# main_P2100.net
KiCad netlist of a schematic drawn in EAGLE
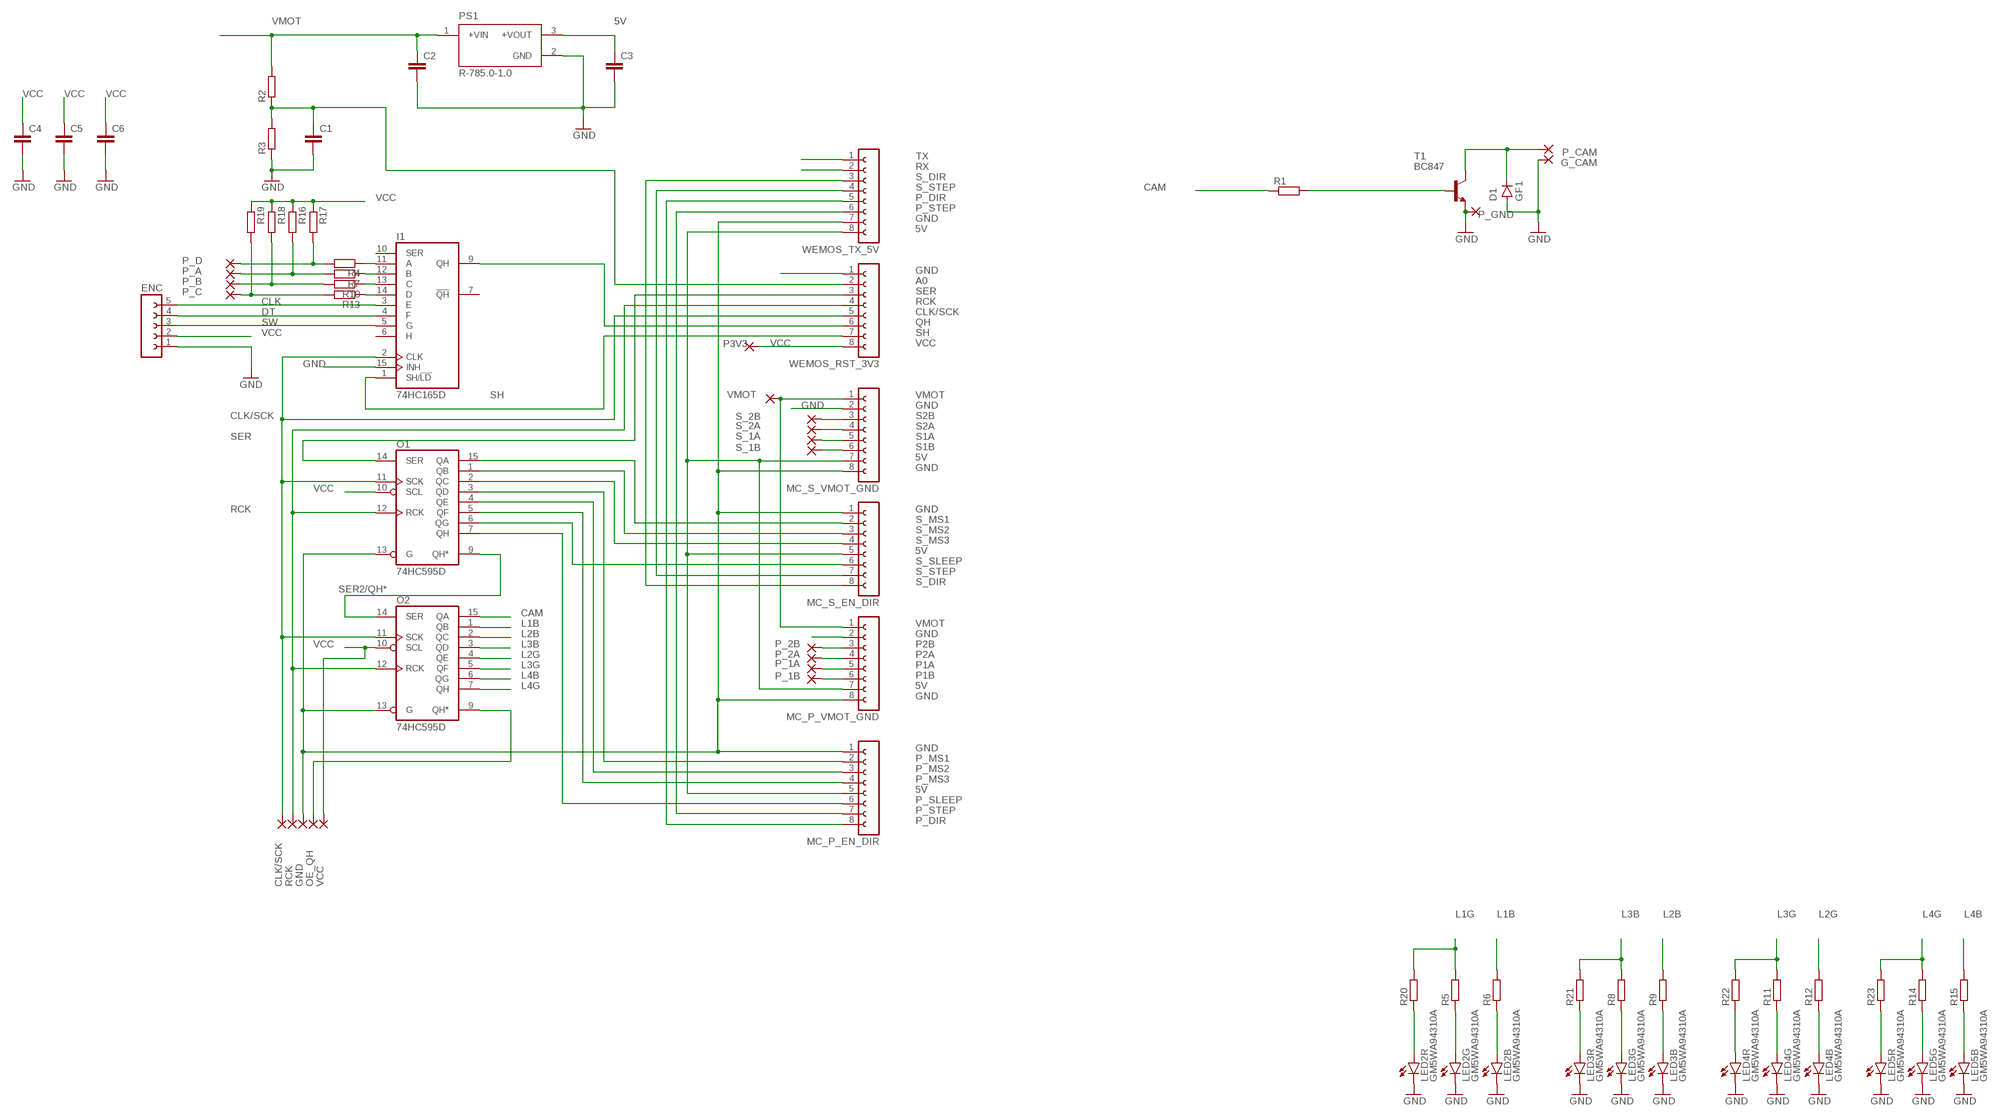
[diagram p0: schematic, sheet 1]

(export (version "E")
  (design (tool "Eeschema 10.0.6"))
  (components
    (comp (ref "C1")
      (value "C-EUC0603")
      (footprint "eagle-import:C0603")
      (libsource (lib "eagle-import") (part "C-EUC0603"))
    )
    (comp (ref "C2")
      (value "C-EUC1206")
      (footprint "eagle-import:C1206")
      (libsource (lib "eagle-import") (part "C-EUC1206"))
    )
    (comp (ref "C3")
      (value "C-EUC1206")
      (footprint "eagle-import:C1206")
      (libsource (lib "eagle-import") (part "C-EUC1206"))
    )
    (comp (ref "C4")
      (value "C-EUC0603")
      (footprint "eagle-import:C0603")
      (libsource (lib "eagle-import") (part "C-EUC0603"))
    )
    (comp (ref "C5")
      (value "C-EUC0603")
      (footprint "eagle-import:C0603")
      (libsource (lib "eagle-import") (part "C-EUC0603"))
    )
    (comp (ref "C6")
      (value "C-EUC0603")
      (footprint "eagle-import:C0603")
      (libsource (lib "eagle-import") (part "C-EUC0603"))
    )
    (comp (ref "D1")
      (value "GF1")
      (footprint "eagle-import:SMA-DO214AC")
      (libsource (lib "eagle-import") (part "GF1"))
    )
    (comp (ref "ENC")
      (value "FE05-1")
      (footprint "eagle-import:FE05-1")
      (libsource (lib "eagle-import") (part "FE05-1"))
    )
    (comp (ref "G_CAM")
      (value "SMD5")
      (footprint "eagle-import:SMD2,54-5,08")
      (libsource (lib "eagle-import") (part "SMD5"))
    )
    (comp (ref "I1")
      (value "74HC165D")
      (footprint "eagle-import:SO16")
      (libsource (lib "eagle-import") (part "74165DHC"))
    )
    (comp (ref "LED2")
      (value "GM5WA94310A")
      (footprint "eagle-import:GM5WA94310A")
      (libsource (lib "eagle-import") (part "GM5WA94310A"))
    )
    (comp (ref "LED3")
      (value "GM5WA94310A")
      (footprint "eagle-import:GM5WA94310A")
      (libsource (lib "eagle-import") (part "GM5WA94310A"))
    )
    (comp (ref "LED4")
      (value "GM5WA94310A")
      (footprint "eagle-import:GM5WA94310A")
      (libsource (lib "eagle-import") (part "GM5WA94310A"))
    )
    (comp (ref "LED5")
      (value "GM5WA94310A")
      (footprint "eagle-import:GM5WA94310A")
      (libsource (lib "eagle-import") (part "GM5WA94310A"))
    )
    (comp (ref "MC_P_EN_DIR")
      (value "FE08-1")
      (footprint "eagle-import:FE08")
      (libsource (lib "eagle-import") (part "FE08-1"))
    )
    (comp (ref "MC_P_VMOT_GND")
      (value "FE08-1")
      (footprint "eagle-import:FE08")
      (libsource (lib "eagle-import") (part "FE08-1"))
    )
    (comp (ref "MC_S_EN_DIR")
      (value "FE08-1")
      (footprint "eagle-import:FE08")
      (libsource (lib "eagle-import") (part "FE08-1"))
    )
    (comp (ref "MC_S_VMOT_GND")
      (value "FE08-1")
      (footprint "eagle-import:FE08")
      (libsource (lib "eagle-import") (part "FE08-1"))
    )
    (comp (ref "O1")
      (value "74HC595D")
      (footprint "eagle-import:SO16")
      (libsource (lib "eagle-import") (part "74595DHC"))
    )
    (comp (ref "O2")
      (value "74HC595D")
      (footprint "eagle-import:SO16")
      (libsource (lib "eagle-import") (part "74595DHC"))
    )
    (comp (ref "P3V3")
      (value "SMD5")
      (footprint "eagle-import:SMD2,54-5,08")
      (libsource (lib "eagle-import") (part "SMD5"))
    )
    (comp (ref "PS1")
      (value "R-785.0-1.0")
      (footprint "eagle-import:CONV_R-785.0-1.0")
      (fields (field (name "MF") "Recom Power"))
      (libsource (lib "eagle-import") (part "R-785.0-1.0"))
    )
    (comp (ref "P_1A")
      (value "SMD5")
      (footprint "eagle-import:SMD2,54-5,08")
      (libsource (lib "eagle-import") (part "SMD5"))
    )
    (comp (ref "P_1B")
      (value "SMD5")
      (footprint "eagle-import:SMD2,54-5,08")
      (libsource (lib "eagle-import") (part "SMD5"))
    )
    (comp (ref "P_1B1")
      (value "SMD5")
      (footprint "eagle-import:SMD2,54-5,08")
      (libsource (lib "eagle-import") (part "SMD5"))
    )
    (comp (ref "P_1B2")
      (value "SMD5")
      (footprint "eagle-import:SMD2,54-5,08")
      (libsource (lib "eagle-import") (part "SMD5"))
    )
    (comp (ref "P_1B3")
      (value "SMD5")
      (footprint "eagle-import:SMD2,54-5,08")
      (libsource (lib "eagle-import") (part "SMD5"))
    )
    (comp (ref "P_1B4")
      (value "SMD5")
      (footprint "eagle-import:SMD2,54-5,08")
      (libsource (lib "eagle-import") (part "SMD5"))
    )
    (comp (ref "P_1B5")
      (value "SMD5")
      (footprint "eagle-import:SMD2,54-5,08")
      (libsource (lib "eagle-import") (part "SMD5"))
    )
    (comp (ref "P_2A")
      (value "SMD5")
      (footprint "eagle-import:SMD2,54-5,08")
      (libsource (lib "eagle-import") (part "SMD5"))
    )
    (comp (ref "P_2B")
      (value "SMD5")
      (footprint "eagle-import:SMD2,54-5,08")
      (libsource (lib "eagle-import") (part "SMD5"))
    )
    (comp (ref "P_A")
      (value "SMD5")
      (footprint "eagle-import:SMD2,54-5,08")
      (libsource (lib "eagle-import") (part "SMD5"))
    )
    (comp (ref "P_B")
      (value "SMD5")
      (footprint "eagle-import:SMD2,54-5,08")
      (libsource (lib "eagle-import") (part "SMD5"))
    )
    (comp (ref "P_C")
      (value "SMD5")
      (footprint "eagle-import:SMD2,54-5,08")
      (libsource (lib "eagle-import") (part "SMD5"))
    )
    (comp (ref "P_CAM")
      (value "SMD5")
      (footprint "eagle-import:SMD2,54-5,08")
      (libsource (lib "eagle-import") (part "SMD5"))
    )
    (comp (ref "P_D")
      (value "SMD5")
      (footprint "eagle-import:SMD2,54-5,08")
      (libsource (lib "eagle-import") (part "SMD5"))
    )
    (comp (ref "P_GND")
      (value "SMD5")
      (footprint "eagle-import:SMD2,54-5,08")
      (libsource (lib "eagle-import") (part "SMD5"))
    )
    (comp (ref "R1")
      (value "R-EU_R0603")
      (footprint "eagle-import:R0603")
      (libsource (lib "eagle-import") (part "R-EU_R0603"))
    )
    (comp (ref "R2")
      (value "R-EU_R0603")
      (footprint "eagle-import:R0603")
      (libsource (lib "eagle-import") (part "R-EU_R0603"))
    )
    (comp (ref "R3")
      (value "R-EU_R0603")
      (footprint "eagle-import:R0603")
      (libsource (lib "eagle-import") (part "R-EU_R0603"))
    )
    (comp (ref "R4")
      (value "R-EU_R0603")
      (footprint "eagle-import:R0603")
      (libsource (lib "eagle-import") (part "R-EU_R0603"))
    )
    (comp (ref "R5")
      (value "R-EU_R0603")
      (footprint "eagle-import:R0603")
      (libsource (lib "eagle-import") (part "R-EU_R0603"))
    )
    (comp (ref "R6")
      (value "R-EU_R0603")
      (footprint "eagle-import:R0603")
      (libsource (lib "eagle-import") (part "R-EU_R0603"))
    )
    (comp (ref "R7")
      (value "R-EU_R0603")
      (footprint "eagle-import:R0603")
      (libsource (lib "eagle-import") (part "R-EU_R0603"))
    )
    (comp (ref "R8")
      (value "R-EU_R0603")
      (footprint "eagle-import:R0603")
      (libsource (lib "eagle-import") (part "R-EU_R0603"))
    )
    (comp (ref "R9")
      (value "R-EU_R0603")
      (footprint "eagle-import:R0603")
      (libsource (lib "eagle-import") (part "R-EU_R0603"))
    )
    (comp (ref "R10")
      (value "R-EU_R0603")
      (footprint "eagle-import:R0603")
      (libsource (lib "eagle-import") (part "R-EU_R0603"))
    )
    (comp (ref "R11")
      (value "R-EU_R0603")
      (footprint "eagle-import:R0603")
      (libsource (lib "eagle-import") (part "R-EU_R0603"))
    )
    (comp (ref "R12")
      (value "R-EU_R0603")
      (footprint "eagle-import:R0603")
      (libsource (lib "eagle-import") (part "R-EU_R0603"))
    )
    (comp (ref "R13")
      (value "R-EU_R0603")
      (footprint "eagle-import:R0603")
      (libsource (lib "eagle-import") (part "R-EU_R0603"))
    )
    (comp (ref "R14")
      (value "R-EU_R0603")
      (footprint "eagle-import:R0603")
      (libsource (lib "eagle-import") (part "R-EU_R0603"))
    )
    (comp (ref "R15")
      (value "R-EU_R0603")
      (footprint "eagle-import:R0603")
      (libsource (lib "eagle-import") (part "R-EU_R0603"))
    )
    (comp (ref "R16")
      (value "R-EU_R0603")
      (footprint "eagle-import:R0603")
      (libsource (lib "eagle-import") (part "R-EU_R0603"))
    )
    (comp (ref "R17")
      (value "R-EU_R0603")
      (footprint "eagle-import:R0603")
      (libsource (lib "eagle-import") (part "R-EU_R0603"))
    )
    (comp (ref "R18")
      (value "R-EU_R0603")
      (footprint "eagle-import:R0603")
      (libsource (lib "eagle-import") (part "R-EU_R0603"))
    )
    (comp (ref "R19")
      (value "R-EU_R0603")
      (footprint "eagle-import:R0603")
      (libsource (lib "eagle-import") (part "R-EU_R0603"))
    )
    (comp (ref "R20")
      (value "R-EU_R0603")
      (footprint "eagle-import:R0603")
      (libsource (lib "eagle-import") (part "R-EU_R0603"))
    )
    (comp (ref "R21")
      (value "R-EU_R0603")
      (footprint "eagle-import:R0603")
      (libsource (lib "eagle-import") (part "R-EU_R0603"))
    )
    (comp (ref "R22")
      (value "R-EU_R0603")
      (footprint "eagle-import:R0603")
      (libsource (lib "eagle-import") (part "R-EU_R0603"))
    )
    (comp (ref "R23")
      (value "R-EU_R0603")
      (footprint "eagle-import:R0603")
      (libsource (lib "eagle-import") (part "R-EU_R0603"))
    )
    (comp (ref "S_1A")
      (value "SMD5")
      (footprint "eagle-import:SMD2,54-5,08")
      (libsource (lib "eagle-import") (part "SMD5"))
    )
    (comp (ref "S_1B")
      (value "SMD5")
      (footprint "eagle-import:SMD2,54-5,08")
      (libsource (lib "eagle-import") (part "SMD5"))
    )
    (comp (ref "S_2A")
      (value "SMD5")
      (footprint "eagle-import:SMD2,54-5,08")
      (libsource (lib "eagle-import") (part "SMD5"))
    )
    (comp (ref "S_2B")
      (value "SMD5")
      (footprint "eagle-import:SMD2,54-5,08")
      (libsource (lib "eagle-import") (part "SMD5"))
    )
    (comp (ref "T1")
      (value "BC847")
      (footprint "eagle-import:SOT23")
      (libsource (lib "eagle-import") (part "BC847"))
    )
    (comp (ref "VMOT")
      (value "SMD5")
      (footprint "eagle-import:SMD2,54-5,08")
      (libsource (lib "eagle-import") (part "SMD5"))
    )
    (comp (ref "WEMOS_RST_3V3")
      (value "FE08-1")
      (footprint "eagle-import:FE08")
      (libsource (lib "eagle-import") (part "FE08-1"))
    )
    (comp (ref "WEMOS_TX_5V")
      (value "FE08-1")
      (footprint "eagle-import:FE08")
      (libsource (lib "eagle-import") (part "FE08-1"))
    )
  )
  (nets
    (net (code "1") (name "/5V") (class "Default")
      (node (ref "C3") (pin "1") (pinfunction "1_1") (pintype "passive"))
      (node (ref "MC_P_EN_DIR") (pin "5") (pinfunction "5_5") (pintype "passive"))
      (node (ref "MC_P_VMOT_GND") (pin "7") (pinfunction "7_7") (pintype "passive"))
      (node (ref "MC_S_EN_DIR") (pin "5") (pinfunction "5_5") (pintype "passive"))
      (node (ref "MC_S_VMOT_GND") (pin "7") (pinfunction "7_7") (pintype "passive"))
      (node (ref "PS1") (pin "3") (pinfunction "+VOUT_3") (pintype "output"))
      (node (ref "WEMOS_TX_5V") (pin "8") (pinfunction "8_8") (pintype "passive"))
    )
    (net (code "2") (name "/A0") (class "Default")
      (node (ref "C1") (pin "1") (pinfunction "1_1") (pintype "passive"))
      (node (ref "R2") (pin "1") (pinfunction "1_1") (pintype "passive"))
      (node (ref "R3") (pin "2") (pinfunction "2_2") (pintype "passive"))
      (node (ref "WEMOS_RST_3V3") (pin "2") (pinfunction "2_2") (pintype "passive"))
    )
    (net (code "3") (name "/CAM") (class "Default")
      (node (ref "O2") (pin "15") (pinfunction "QA_15") (pintype "tri_state"))
      (node (ref "R1") (pin "1") (pinfunction "1_1") (pintype "passive"))
    )
    (net (code "4") (name "/CLK") (class "Default")
      (node (ref "ENC") (pin "5") (pinfunction "5_5") (pintype "passive"))
      (node (ref "I1") (pin "3") (pinfunction "E_3") (pintype "input"))
    )
    (net (code "5") (name "/CLK{slash}SCK") (class "Default")
      (node (ref "I1") (pin "2") (pinfunction "CLK_2") (pintype "input"))
      (node (ref "O1") (pin "11") (pinfunction "SCK_11") (pintype "input"))
      (node (ref "O2") (pin "11") (pinfunction "SCK_11") (pintype "input"))
      (node (ref "P_1B1") (pin "1") (pinfunction "P_1") (pintype "passive"))
      (node (ref "WEMOS_RST_3V3") (pin "5") (pinfunction "5_5") (pintype "passive"))
    )
    (net (code "6") (name "/DT") (class "Default")
      (node (ref "ENC") (pin "4") (pinfunction "4_4") (pintype "passive"))
      (node (ref "I1") (pin "4") (pinfunction "F_4") (pintype "input"))
    )
    (net (code "7") (name "/L1B") (class "Default")
      (node (ref "O2") (pin "1") (pinfunction "QB_1") (pintype "tri_state"))
      (node (ref "R6") (pin "2") (pinfunction "2_2") (pintype "passive"))
    )
    (net (code "8") (name "/L1G") (class "Default")
      (node (ref "R20") (pin "2") (pinfunction "2_2") (pintype "passive"))
      (node (ref "R5") (pin "2") (pinfunction "2_2") (pintype "passive"))
    )
    (net (code "9") (name "/L2B") (class "Default")
      (node (ref "O2") (pin "2") (pinfunction "QC_2") (pintype "tri_state"))
      (node (ref "R9") (pin "2") (pinfunction "2_2") (pintype "passive"))
    )
    (net (code "10") (name "/L2G") (class "Default")
      (node (ref "O2") (pin "4") (pinfunction "QE_4") (pintype "tri_state"))
      (node (ref "R12") (pin "2") (pinfunction "2_2") (pintype "passive"))
    )
    (net (code "11") (name "/L3B") (class "Default")
      (node (ref "O2") (pin "3") (pinfunction "QD_3") (pintype "tri_state"))
      (node (ref "R21") (pin "2") (pinfunction "2_2") (pintype "passive"))
      (node (ref "R8") (pin "2") (pinfunction "2_2") (pintype "passive"))
    )
    (net (code "12") (name "/L3G") (class "Default")
      (node (ref "O2") (pin "5") (pinfunction "QF_5") (pintype "tri_state"))
      (node (ref "R11") (pin "2") (pinfunction "2_2") (pintype "passive"))
      (node (ref "R22") (pin "2") (pinfunction "2_2") (pintype "passive"))
    )
    (net (code "13") (name "/L4B") (class "Default")
      (node (ref "O2") (pin "6") (pinfunction "QG_6") (pintype "tri_state"))
      (node (ref "R15") (pin "2") (pinfunction "2_2") (pintype "passive"))
    )
    (net (code "14") (name "/L4G") (class "Default")
      (node (ref "O2") (pin "7") (pinfunction "QH_7") (pintype "tri_state"))
      (node (ref "R14") (pin "2") (pinfunction "2_2") (pintype "passive"))
      (node (ref "R23") (pin "2") (pinfunction "2_2") (pintype "passive"))
    )
    (net (code "15") (name "/OE_QH") (class "Default")
      (node (ref "O2") (pin "9") (pinfunction "QH*_9") (pintype "tri_state"))
      (node (ref "P_1B4") (pin "1") (pinfunction "P_1") (pintype "passive"))
    )
    (net (code "16") (name "/P1A") (class "Default")
      (node (ref "MC_P_VMOT_GND") (pin "5") (pinfunction "5_5") (pintype "passive"))
      (node (ref "P_1A") (pin "1") (pinfunction "P_1") (pintype "passive"))
    )
    (net (code "17") (name "/P1B") (class "Default")
      (node (ref "MC_P_VMOT_GND") (pin "6") (pinfunction "6_6") (pintype "passive"))
      (node (ref "P_1B") (pin "1") (pinfunction "P_1") (pintype "passive"))
    )
    (net (code "18") (name "/P2A") (class "Default")
      (node (ref "MC_P_VMOT_GND") (pin "4") (pinfunction "4_4") (pintype "passive"))
      (node (ref "P_2A") (pin "1") (pinfunction "P_1") (pintype "passive"))
    )
    (net (code "19") (name "/P2B") (class "Default")
      (node (ref "MC_P_VMOT_GND") (pin "3") (pinfunction "3_3") (pintype "passive"))
      (node (ref "P_2B") (pin "1") (pinfunction "P_1") (pintype "passive"))
    )
    (net (code "20") (name "/P_DIR") (class "Default")
      (node (ref "MC_P_EN_DIR") (pin "8") (pinfunction "8_8") (pintype "passive"))
      (node (ref "WEMOS_TX_5V") (pin "5") (pinfunction "5_5") (pintype "passive"))
    )
    (net (code "21") (name "/P_MS1") (class "Default")
      (node (ref "MC_P_EN_DIR") (pin "2") (pinfunction "2_2") (pintype "passive"))
      (node (ref "O1") (pin "3") (pinfunction "QD_3") (pintype "tri_state"))
    )
    (net (code "22") (name "/P_MS2") (class "Default")
      (node (ref "MC_P_EN_DIR") (pin "3") (pinfunction "3_3") (pintype "passive"))
      (node (ref "O1") (pin "4") (pinfunction "QE_4") (pintype "tri_state"))
    )
    (net (code "23") (name "/P_MS3") (class "Default")
      (node (ref "MC_P_EN_DIR") (pin "4") (pinfunction "4_4") (pintype "passive"))
      (node (ref "O1") (pin "5") (pinfunction "QF_5") (pintype "tri_state"))
    )
    (net (code "24") (name "/P_SLEEP") (class "Default")
      (node (ref "MC_P_EN_DIR") (pin "6") (pinfunction "6_6") (pintype "passive"))
      (node (ref "O1") (pin "7") (pinfunction "QH_7") (pintype "tri_state"))
    )
    (net (code "25") (name "/P_STEP") (class "Default")
      (node (ref "MC_P_EN_DIR") (pin "7") (pinfunction "7_7") (pintype "passive"))
      (node (ref "WEMOS_TX_5V") (pin "6") (pinfunction "6_6") (pintype "passive"))
    )
    (net (code "26") (name "/QH") (class "Default")
      (node (ref "I1") (pin "9") (pinfunction "QH_9") (pintype "output"))
      (node (ref "WEMOS_RST_3V3") (pin "6") (pinfunction "6_6") (pintype "passive"))
    )
    (net (code "27") (name "/RCK") (class "Default")
      (node (ref "O1") (pin "12") (pinfunction "RCK_12") (pintype "input"))
      (node (ref "O2") (pin "12") (pinfunction "RCK_12") (pintype "input"))
      (node (ref "P_1B2") (pin "1") (pinfunction "P_1") (pintype "passive"))
      (node (ref "WEMOS_RST_3V3") (pin "4") (pinfunction "4_4") (pintype "passive"))
    )
    (net (code "28") (name "/RX") (class "Default")
      (node (ref "WEMOS_TX_5V") (pin "2") (pinfunction "2_2") (pintype "passive"))
    )
    (net (code "29") (name "/S1A") (class "Default")
      (node (ref "MC_S_VMOT_GND") (pin "5") (pinfunction "5_5") (pintype "passive"))
      (node (ref "S_1A") (pin "1") (pinfunction "P_1") (pintype "passive"))
    )
    (net (code "30") (name "/S1B") (class "Default")
      (node (ref "MC_S_VMOT_GND") (pin "6") (pinfunction "6_6") (pintype "passive"))
      (node (ref "S_1B") (pin "1") (pinfunction "P_1") (pintype "passive"))
    )
    (net (code "31") (name "/S2A") (class "Default")
      (node (ref "MC_S_VMOT_GND") (pin "4") (pinfunction "4_4") (pintype "passive"))
      (node (ref "S_2A") (pin "1") (pinfunction "P_1") (pintype "passive"))
    )
    (net (code "32") (name "/S2B") (class "Default")
      (node (ref "MC_S_VMOT_GND") (pin "3") (pinfunction "3_3") (pintype "passive"))
      (node (ref "S_2B") (pin "1") (pinfunction "P_1") (pintype "passive"))
    )
    (net (code "33") (name "/SER") (class "Default")
      (node (ref "O1") (pin "14") (pinfunction "SER_14") (pintype "input"))
      (node (ref "WEMOS_RST_3V3") (pin "3") (pinfunction "3_3") (pintype "passive"))
    )
    (net (code "34") (name "/SER2{slash}QH*") (class "Default")
      (node (ref "O1") (pin "9") (pinfunction "QH*_9") (pintype "tri_state"))
      (node (ref "O2") (pin "14") (pinfunction "SER_14") (pintype "input"))
    )
    (net (code "35") (name "/SH") (class "Default")
      (node (ref "I1") (pin "1") (pinfunction "SH/~{LD}_1") (pintype "input"))
      (node (ref "WEMOS_RST_3V3") (pin "7") (pinfunction "7_7") (pintype "passive"))
    )
    (net (code "36") (name "/SW") (class "Default")
      (node (ref "ENC") (pin "3") (pinfunction "3_3") (pintype "passive"))
      (node (ref "I1") (pin "5") (pinfunction "G_5") (pintype "input"))
    )
    (net (code "37") (name "/S_DIR") (class "Default")
      (node (ref "MC_S_EN_DIR") (pin "8") (pinfunction "8_8") (pintype "passive"))
      (node (ref "WEMOS_TX_5V") (pin "3") (pinfunction "3_3") (pintype "passive"))
    )
    (net (code "38") (name "/S_MS1") (class "Default")
      (node (ref "MC_S_EN_DIR") (pin "2") (pinfunction "2_2") (pintype "passive"))
      (node (ref "O1") (pin "15") (pinfunction "QA_15") (pintype "tri_state"))
    )
    (net (code "39") (name "/S_MS2") (class "Default")
      (node (ref "MC_S_EN_DIR") (pin "3") (pinfunction "3_3") (pintype "passive"))
      (node (ref "O1") (pin "1") (pinfunction "QB_1") (pintype "tri_state"))
    )
    (net (code "40") (name "/S_MS3") (class "Default")
      (node (ref "MC_S_EN_DIR") (pin "4") (pinfunction "4_4") (pintype "passive"))
      (node (ref "O1") (pin "2") (pinfunction "QC_2") (pintype "tri_state"))
    )
    (net (code "41") (name "/S_SLEEP") (class "Default")
      (node (ref "MC_S_EN_DIR") (pin "6") (pinfunction "6_6") (pintype "passive"))
      (node (ref "O1") (pin "6") (pinfunction "QG_6") (pintype "tri_state"))
    )
    (net (code "42") (name "/S_STEP") (class "Default")
      (node (ref "MC_S_EN_DIR") (pin "7") (pinfunction "7_7") (pintype "passive"))
      (node (ref "WEMOS_TX_5V") (pin "4") (pinfunction "4_4") (pintype "passive"))
    )
    (net (code "43") (name "/TX") (class "Default")
      (node (ref "WEMOS_TX_5V") (pin "1") (pinfunction "1_1") (pintype "passive"))
    )
    (net (code "44") (name "/VCC") (class "Default")
      (node (ref "C4") (pin "1") (pinfunction "1_1") (pintype "passive"))
      (node (ref "C5") (pin "1") (pinfunction "1_1") (pintype "passive"))
      (node (ref "C6") (pin "1") (pinfunction "1_1") (pintype "passive"))
      (node (ref "ENC") (pin "2") (pinfunction "2_2") (pintype "passive"))
      (node (ref "O1") (pin "10") (pinfunction "SCL_10") (pintype "input"))
      (node (ref "O2") (pin "10") (pinfunction "SCL_10") (pintype "input"))
      (node (ref "P3V3") (pin "1") (pinfunction "P_1") (pintype "passive"))
      (node (ref "P_1B5") (pin "1") (pinfunction "P_1") (pintype "passive"))
      (node (ref "R16") (pin "1") (pinfunction "1_1") (pintype "passive"))
      (node (ref "R17") (pin "1") (pinfunction "1_1") (pintype "passive"))
      (node (ref "R18") (pin "1") (pinfunction "1_1") (pintype "passive"))
      (node (ref "R19") (pin "1") (pinfunction "1_1") (pintype "passive"))
      (node (ref "WEMOS_RST_3V3") (pin "8") (pinfunction "8_8") (pintype "passive"))
    )
    (net (code "45") (name "/VMOT") (class "Default")
      (node (ref "C2") (pin "1") (pinfunction "1_1") (pintype "passive"))
      (node (ref "MC_P_VMOT_GND") (pin "1") (pinfunction "1_1") (pintype "passive"))
      (node (ref "MC_S_VMOT_GND") (pin "1") (pinfunction "1_1") (pintype "passive"))
      (node (ref "PS1") (pin "1") (pinfunction "+VIN_1") (pintype "input"))
      (node (ref "R2") (pin "2") (pinfunction "2_2") (pintype "passive"))
      (node (ref "VMOT") (pin "1") (pinfunction "P_1") (pintype "passive"))
    )
    (net (code "46") (name "GND") (class "Default")
      (node (ref "C1") (pin "2") (pinfunction "2_2") (pintype "passive"))
      (node (ref "C2") (pin "2") (pinfunction "2_2") (pintype "passive"))
      (node (ref "C3") (pin "2") (pinfunction "2_2") (pintype "passive"))
      (node (ref "C4") (pin "2") (pinfunction "2_2") (pintype "passive"))
      (node (ref "C5") (pin "2") (pinfunction "2_2") (pintype "passive"))
      (node (ref "C6") (pin "2") (pinfunction "2_2") (pintype "passive"))
      (node (ref "D1") (pin "A") (pinfunction "A_A") (pintype "passive"))
      (node (ref "ENC") (pin "1") (pinfunction "1_1") (pintype "passive"))
      (node (ref "G_CAM") (pin "1") (pinfunction "P_1") (pintype "passive"))
      (node (ref "I1") (pin "15") (pinfunction "INH_15") (pintype "input"))
      (node (ref "LED2") (pin "4") (pinfunction "C_4") (pintype "passive"))
      (node (ref "LED2") (pin "5") (pinfunction "C_5") (pintype "passive"))
      (node (ref "LED2") (pin "6") (pinfunction "C_6") (pintype "passive"))
      (node (ref "LED3") (pin "4") (pinfunction "C_4") (pintype "passive"))
      (node (ref "LED3") (pin "5") (pinfunction "C_5") (pintype "passive"))
      (node (ref "LED3") (pin "6") (pinfunction "C_6") (pintype "passive"))
      (node (ref "LED4") (pin "4") (pinfunction "C_4") (pintype "passive"))
      (node (ref "LED4") (pin "5") (pinfunction "C_5") (pintype "passive"))
      (node (ref "LED4") (pin "6") (pinfunction "C_6") (pintype "passive"))
      (node (ref "LED5") (pin "4") (pinfunction "C_4") (pintype "passive"))
      (node (ref "LED5") (pin "5") (pinfunction "C_5") (pintype "passive"))
      (node (ref "LED5") (pin "6") (pinfunction "C_6") (pintype "passive"))
      (node (ref "MC_P_EN_DIR") (pin "1") (pinfunction "1_1") (pintype "passive"))
      (node (ref "MC_P_VMOT_GND") (pin "2") (pinfunction "2_2") (pintype "passive"))
      (node (ref "MC_P_VMOT_GND") (pin "8") (pinfunction "8_8") (pintype "passive"))
      (node (ref "MC_S_EN_DIR") (pin "1") (pinfunction "1_1") (pintype "passive"))
      (node (ref "MC_S_VMOT_GND") (pin "2") (pinfunction "2_2") (pintype "passive"))
      (node (ref "MC_S_VMOT_GND") (pin "8") (pinfunction "8_8") (pintype "passive"))
      (node (ref "O1") (pin "13") (pinfunction "G_13") (pintype "input"))
      (node (ref "O2") (pin "13") (pinfunction "G_13") (pintype "input"))
      (node (ref "PS1") (pin "2") (pinfunction "GND_2") (pintype "power_in"))
      (node (ref "P_1B3") (pin "1") (pinfunction "P_1") (pintype "passive"))
      (node (ref "P_GND") (pin "1") (pinfunction "P_1") (pintype "passive"))
      (node (ref "R3") (pin "1") (pinfunction "1_1") (pintype "passive"))
      (node (ref "T1") (pin "2") (pinfunction "E_2") (pintype "passive"))
      (node (ref "WEMOS_RST_3V3") (pin "1") (pinfunction "1_1") (pintype "passive"))
      (node (ref "WEMOS_TX_5V") (pin "7") (pinfunction "7_7") (pintype "passive"))
    )
    (net (code "47") (name "Net-(D1-C)") (class "Default")
      (node (ref "D1") (pin "K") (pinfunction "C_K") (pintype "passive"))
      (node (ref "P_CAM") (pin "1") (pinfunction "P_1") (pintype "passive"))
      (node (ref "T1") (pin "3") (pinfunction "C_3") (pintype "passive"))
    )
    (net (code "48") (name "Net-(I1A-A)") (class "Default")
      (node (ref "I1") (pin "11") (pinfunction "A_11") (pintype "input"))
      (node (ref "R4") (pin "1") (pinfunction "1_1") (pintype "passive"))
    )
    (net (code "49") (name "Net-(I1A-B)") (class "Default")
      (node (ref "I1") (pin "12") (pinfunction "B_12") (pintype "input"))
      (node (ref "R7") (pin "1") (pinfunction "1_1") (pintype "passive"))
    )
    (net (code "50") (name "Net-(I1A-C)") (class "Default")
      (node (ref "I1") (pin "13") (pinfunction "C_13") (pintype "input"))
      (node (ref "R10") (pin "1") (pinfunction "1_1") (pintype "passive"))
    )
    (net (code "51") (name "Net-(I1A-D)") (class "Default")
      (node (ref "I1") (pin "14") (pinfunction "D_14") (pintype "input"))
      (node (ref "R13") (pin "1") (pinfunction "1_1") (pintype "passive"))
    )
    (net (code "52") (name "Net-(LED2A-A)") (class "Default")
      (node (ref "LED2") (pin "1") (pinfunction "A_1") (pintype "passive"))
      (node (ref "R6") (pin "1") (pinfunction "1_1") (pintype "passive"))
    )
    (net (code "53") (name "Net-(LED2B-A)") (class "Default")
      (node (ref "LED2") (pin "3") (pinfunction "A_3") (pintype "passive"))
      (node (ref "R5") (pin "1") (pinfunction "1_1") (pintype "passive"))
    )
    (net (code "54") (name "Net-(LED2C-A)") (class "Default")
      (node (ref "LED2") (pin "2") (pinfunction "A_2") (pintype "passive"))
      (node (ref "R20") (pin "1") (pinfunction "1_1") (pintype "passive"))
    )
    (net (code "55") (name "Net-(LED3A-A)") (class "Default")
      (node (ref "LED3") (pin "1") (pinfunction "A_1") (pintype "passive"))
      (node (ref "R9") (pin "1") (pinfunction "1_1") (pintype "passive"))
    )
    (net (code "56") (name "Net-(LED3B-A)") (class "Default")
      (node (ref "LED3") (pin "3") (pinfunction "A_3") (pintype "passive"))
      (node (ref "R8") (pin "1") (pinfunction "1_1") (pintype "passive"))
    )
    (net (code "57") (name "Net-(LED3C-A)") (class "Default")
      (node (ref "LED3") (pin "2") (pinfunction "A_2") (pintype "passive"))
      (node (ref "R21") (pin "1") (pinfunction "1_1") (pintype "passive"))
    )
    (net (code "58") (name "Net-(LED4A-A)") (class "Default")
      (node (ref "LED4") (pin "1") (pinfunction "A_1") (pintype "passive"))
      (node (ref "R12") (pin "1") (pinfunction "1_1") (pintype "passive"))
    )
    (net (code "59") (name "Net-(LED4B-A)") (class "Default")
      (node (ref "LED4") (pin "3") (pinfunction "A_3") (pintype "passive"))
      (node (ref "R11") (pin "1") (pinfunction "1_1") (pintype "passive"))
    )
    (net (code "60") (name "Net-(LED4C-A)") (class "Default")
      (node (ref "LED4") (pin "2") (pinfunction "A_2") (pintype "passive"))
      (node (ref "R22") (pin "1") (pinfunction "1_1") (pintype "passive"))
    )
    (net (code "61") (name "Net-(LED5A-A)") (class "Default")
      (node (ref "LED5") (pin "1") (pinfunction "A_1") (pintype "passive"))
      (node (ref "R15") (pin "1") (pinfunction "1_1") (pintype "passive"))
    )
    (net (code "62") (name "Net-(LED5B-A)") (class "Default")
      (node (ref "LED5") (pin "3") (pinfunction "A_3") (pintype "passive"))
      (node (ref "R14") (pin "1") (pinfunction "1_1") (pintype "passive"))
    )
    (net (code "63") (name "Net-(LED5C-A)") (class "Default")
      (node (ref "LED5") (pin "2") (pinfunction "A_2") (pintype "passive"))
      (node (ref "R23") (pin "1") (pinfunction "1_1") (pintype "passive"))
    )
    (net (code "64") (name "Net-(P_A-P)") (class "Default")
      (node (ref "P_A") (pin "1") (pinfunction "P_1") (pintype "passive"))
      (node (ref "R16") (pin "2") (pinfunction "2_2") (pintype "passive"))
      (node (ref "R7") (pin "2") (pinfunction "2_2") (pintype "passive"))
    )
    (net (code "65") (name "Net-(P_B-P)") (class "Default")
      (node (ref "P_B") (pin "1") (pinfunction "P_1") (pintype "passive"))
      (node (ref "R10") (pin "2") (pinfunction "2_2") (pintype "passive"))
      (node (ref "R18") (pin "2") (pinfunction "2_2") (pintype "passive"))
    )
    (net (code "66") (name "Net-(P_C-P)") (class "Default")
      (node (ref "P_C") (pin "1") (pinfunction "P_1") (pintype "passive"))
      (node (ref "R13") (pin "2") (pinfunction "2_2") (pintype "passive"))
      (node (ref "R19") (pin "2") (pinfunction "2_2") (pintype "passive"))
    )
    (net (code "67") (name "Net-(P_D-P)") (class "Default")
      (node (ref "P_D") (pin "1") (pinfunction "P_1") (pintype "passive"))
      (node (ref "R17") (pin "2") (pinfunction "2_2") (pintype "passive"))
      (node (ref "R4") (pin "2") (pinfunction "2_2") (pintype "passive"))
    )
    (net (code "68") (name "Net-(T1-B)") (class "Default")
      (node (ref "R1") (pin "2") (pinfunction "2_2") (pintype "passive"))
      (node (ref "T1") (pin "1") (pinfunction "B_1") (pintype "passive"))
    )
    (net (code "69") (name "unconnected-(I1A-H-Pad6)") (class "Default")
      (node (ref "I1") (pin "6") (pinfunction "H_6") (pintype "input"))
    )
    (net (code "70") (name "unconnected-(I1A-SER-Pad10)") (class "Default")
      (node (ref "I1") (pin "10") (pinfunction "SER_10") (pintype "input"))
    )
    (net (code "71") (name "unconnected-(I1A-~{QH}-Pad7)") (class "Default")
      (node (ref "I1") (pin "7") (pinfunction "~{QH}_7") (pintype "output"))
    )
  )
)
